# Buck_Converter.net
KiCad netlist of a schematic drawn in Altium Designer
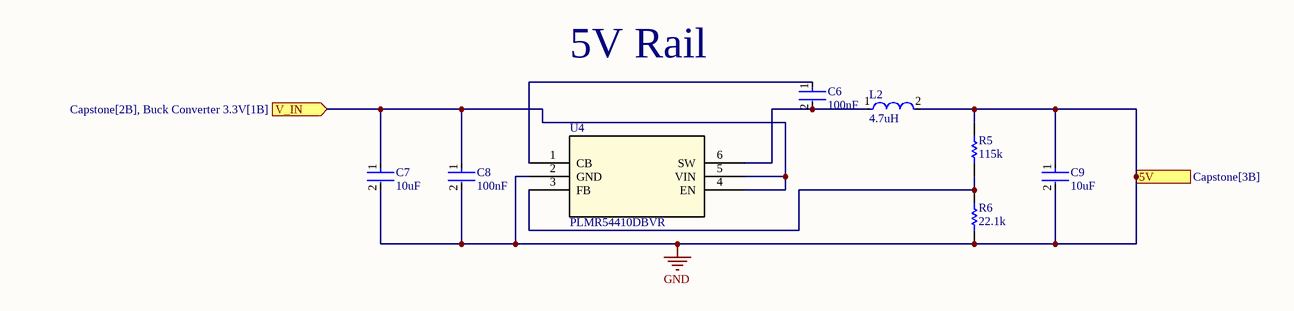
[diagram p0: Buck Converter.SchDoc]

(export (version "E")
  (design (tool "Eeschema 10.0.6"))
  (components
    (comp (ref "C6")
      (value "100nF")
      (footprint "FP-C0805C-DN-MFG")
      (description "CAP CER 0.22UF 50V X7R 0805")
      (fields
        (field (name "MANUFACTURER") "KEMET")
        (field (name "OCTOPART") "https://octopart.com/c0805c224k5ractu-kemet-144670")
      )
      (libsource (lib "Altium Content Vault") (part "b4654b650e69147ec39a6b967a45e02"))
    )
    (comp (ref "C7")
      (value "10uF")
      (footprint "FP-C0805C-DN-MFG")
      (description "CAP CER 0.22UF 50V X7R 0805")
      (fields
        (field (name "MANUFACTURER") "KEMET")
        (field (name "OCTOPART") "https://octopart.com/c0805c224k5ractu-kemet-144670")
      )
      (libsource (lib "Altium Content Vault") (part "b4654b650e69147ec39a6b967a45e02"))
    )
    (comp (ref "C8")
      (value "100nF")
      (footprint "FP-C0805C-DN-MFG")
      (description "CAP CER 0.22UF 50V X7R 0805")
      (fields
        (field (name "MANUFACTURER") "KEMET")
        (field (name "OCTOPART") "https://octopart.com/c0805c224k5ractu-kemet-144670")
      )
      (libsource (lib "Altium Content Vault") (part "b4654b650e69147ec39a6b967a45e02"))
    )
    (comp (ref "C9")
      (value "10uF")
      (footprint "FP-C0805C-DN-MFG")
      (description "CAP CER 0.22UF 50V X7R 0805")
      (fields
        (field (name "MANUFACTURER") "KEMET")
        (field (name "OCTOPART") "https://octopart.com/c0805c224k5ractu-kemet-144670")
      )
      (libsource (lib "Altium Content Vault") (part "b4654b650e69147ec39a6b967a45e02"))
    )
    (comp (ref "L2")
      (value "4.7uH")
      (footprint "FP-LQM21PH_G0-IPC_C")
      (description "Multilayer Type Inductor for Power Lines, 0805 (2012), 4.7μH, 20%, 0.288Ω, 0.8A")
      (fields (field (name "TOLERANCE") "20%"))
      (libsource (lib "Altium Content Vault") (part "725321dda6339637d4d059423bc1c3c"))
    )
    (comp (ref "R5")
      (value "115k")
      (footprint "RESC1608X55X25ML10T15")
      (description "Chip Resistor, 0 Ohm, +/- 5%, 0.1 W, -55 to 155 degC, 0603 (1608 Metric), RoHS, Tape and Reel")
      (fields (field (name "TOLERANCE") "5%") (field (name "MANUFACTURER") "Yageo"))
      (libsource (lib "Altium Content Vault") (part "RES-2"))
    )
    (comp (ref "R6")
      (value "22.1k")
      (footprint "RESC1608X55X25ML10T15")
      (description "Chip Resistor, 0 Ohm, +/- 5%, 0.1 W, -55 to 155 degC, 0603 (1608 Metric), RoHS, Tape and Reel")
      (fields (field (name "TOLERANCE") "5%") (field (name "MANUFACTURER") "Yageo"))
      (libsource (lib "Altium Content Vault") (part "RES-2"))
    )
    (comp (ref "U4")
      (value "PLMR54410DBVR")
      (footprint "U_SOT-23_TEX")
      (description "No Description Available")
      (libsource (lib "PLMR54410DBVR") (part "PLMR54410DBVR"))
    )
  )
  (nets
    (net (code "1") (name "/V_IN") (class "Default")
      (node (ref "C7") (pin "1") (pinfunction "1_1") (pintype "passive"))
      (node (ref "C8") (pin "1") (pinfunction "1_1") (pintype "passive"))
      (node (ref "U4") (pin "4") (pinfunction "EN_4") (pintype "passive"))
      (node (ref "U4") (pin "5") (pinfunction "VIN_5") (pintype "passive"))
    )
    (net (code "2") (name "GND") (class "Default")
      (node (ref "C7") (pin "2") (pinfunction "2_2") (pintype "passive"))
      (node (ref "C8") (pin "2") (pinfunction "2_2") (pintype "passive"))
      (node (ref "C9") (pin "1") (pinfunction "1_1") (pintype "passive"))
      (node (ref "C9") (pin "2") (pinfunction "2_2") (pintype "passive"))
      (node (ref "L2") (pin "2") (pinfunction "2_2") (pintype "passive"))
      (node (ref "R5") (pin "2") (pinfunction "2_2") (pintype "passive"))
      (node (ref "R6") (pin "1") (pinfunction "1_1") (pintype "passive"))
      (node (ref "U4") (pin "2") (pinfunction "GND_2") (pintype "passive"))
    )
    (net (code "3") (name "Net-(U4-CB)") (class "Default")
      (node (ref "C6") (pin "1") (pinfunction "1_1") (pintype "passive"))
      (node (ref "U4") (pin "1") (pinfunction "CB_1") (pintype "power_in"))
    )
    (net (code "4") (name "Net-(U4-FB)") (class "Default")
      (node (ref "R5") (pin "1") (pinfunction "1_1") (pintype "passive"))
      (node (ref "R6") (pin "2") (pinfunction "2_2") (pintype "passive"))
      (node (ref "U4") (pin "3") (pinfunction "FB_3") (pintype "passive"))
    )
    (net (code "5") (name "Net-(U4-SW)") (class "Default")
      (node (ref "C6") (pin "2") (pinfunction "2_2") (pintype "passive"))
      (node (ref "L2") (pin "1") (pinfunction "1_1") (pintype "passive"))
      (node (ref "U4") (pin "6") (pinfunction "SW_6") (pintype "power_in"))
    )
  )
)
